# SWD.net
KiCad netlist of a schematic drawn in Altium Designer
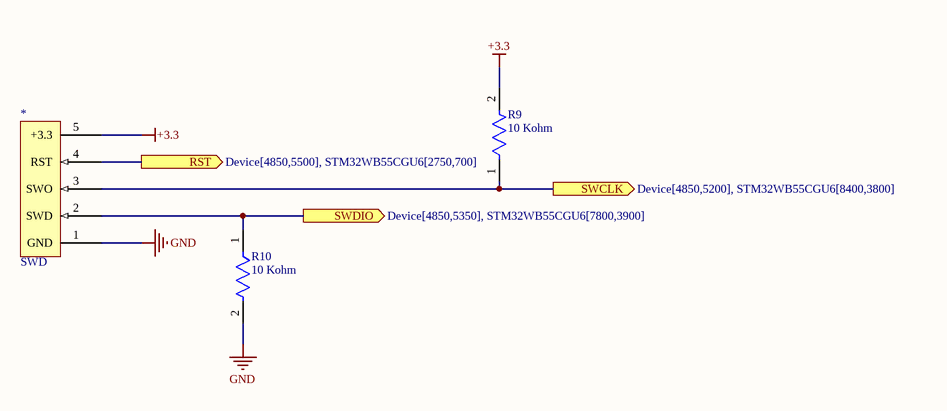
[diagram p0: SWD.SchDoc]

(export (version "E")
  (design (tool "Eeschema 10.0.6"))
  (components
    (comp (ref "*") (value "SWD") (footprint "PCBComponent_1") (libsource (lib "Custom.") (part "SWD")))
    (comp (ref "R9")
      (value "10 Kohm")
      (footprint "FP-RC1005-IPC_C")
      (description "Res Thick Film 0402 1.87kΩ 1% 0.063W ±100ppm/°C Molded SMD T/R")
      (fields (field (name "TOLERANCE") "1%"))
      (libsource (lib "Altium Content Vault") (part "1029c3af85768c4190bb7ad29bc67b5"))
    )
    (comp (ref "R10")
      (value "10 Kohm")
      (footprint "FP-RC1005-IPC_C")
      (description "Res Thick Film 0402 1.87kΩ 1% 0.063W ±100ppm/°C Molded SMD T/R")
      (fields (field (name "TOLERANCE") "1%"))
      (libsource (lib "Altium Content Vault") (part "1029c3af85768c4190bb7ad29bc67b5"))
    )
  )
  (nets
    (net (code "1") (name "+3.3") (class "Default")
      (node (ref "*") (pin "5") (pinfunction "+3.3_5") (pintype "power_in"))
      (node (ref "R9") (pin "2") (pinfunction "2_2") (pintype "passive"))
    )
    (net (code "2") (name "/RST") (class "Default")
      (node (ref "*") (pin "4") (pinfunction "RST_4") (pintype "input"))
    )
    (net (code "3") (name "/SWCLK") (class "Default")
      (node (ref "*") (pin "3") (pinfunction "SWO_3") (pintype "input"))
      (node (ref "R9") (pin "1") (pinfunction "1_1") (pintype "passive"))
    )
    (net (code "4") (name "/SWDIO") (class "Default")
      (node (ref "*") (pin "2") (pinfunction "SWD_2") (pintype "input"))
      (node (ref "R10") (pin "1") (pinfunction "1_1") (pintype "passive"))
    )
    (net (code "5") (name "GND") (class "Default")
      (node (ref "*") (pin "1") (pinfunction "GND_1") (pintype "power_in"))
      (node (ref "R10") (pin "2") (pinfunction "2_2") (pintype "passive"))
    )
  )
)
